# MCU.net
KiCad netlist of a schematic drawn in Altium Designer
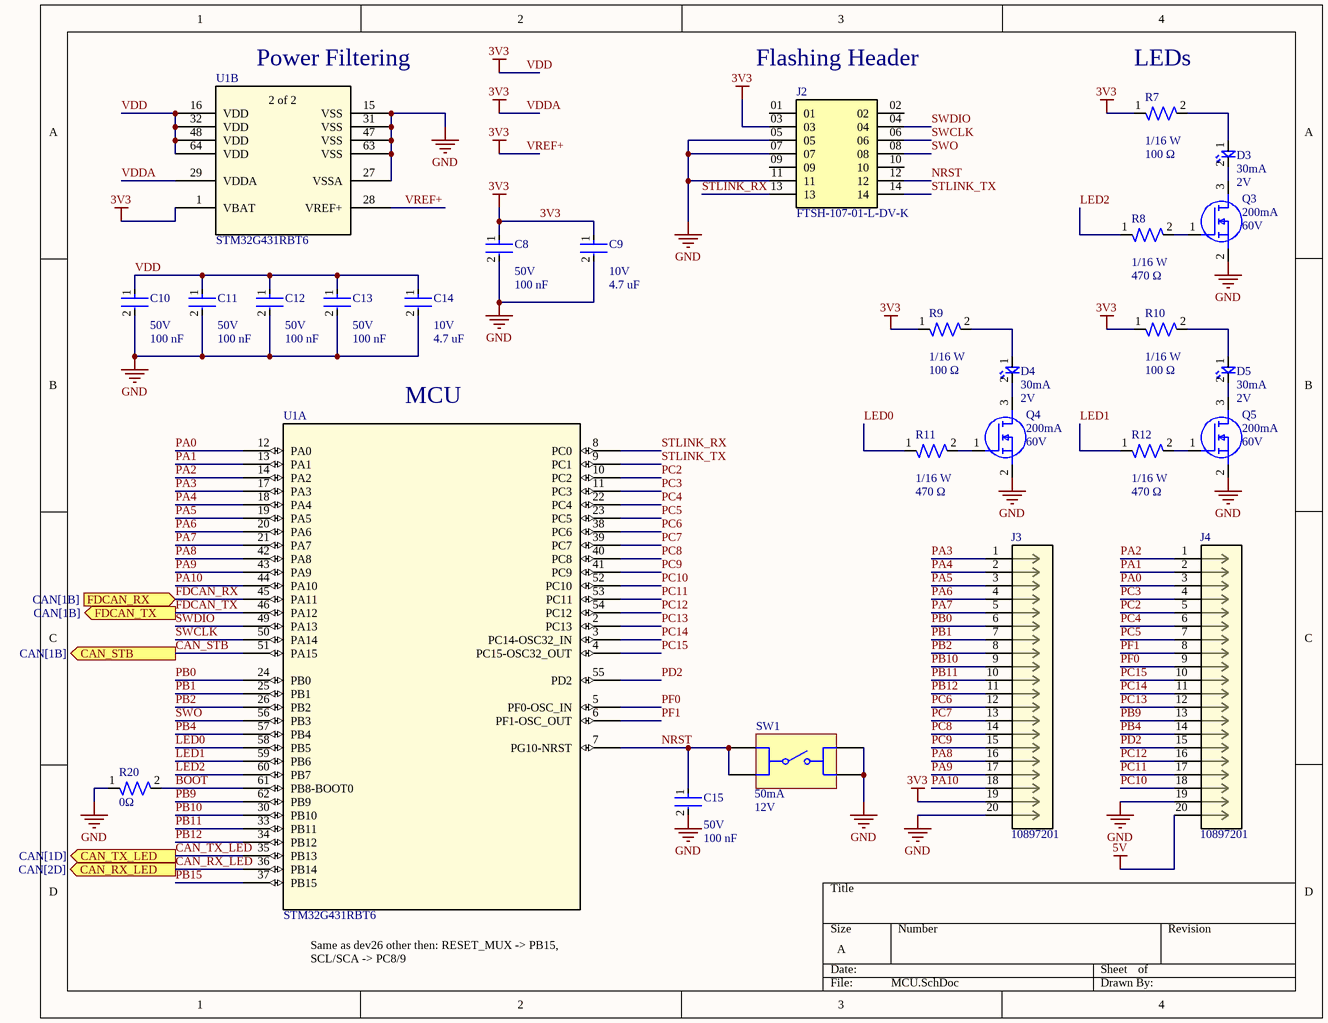
[diagram p0: MCU.SchDoc]

(export (version "E")
  (design (tool "Eeschema 10.0.6"))
  (components
    (comp (ref "C8")
      (value "CC0603ZRY5V9BB104")
      (footprint "CAP-0603")
      (fields (field (name "VOLTAGE RATING") "50V") (field (name "CAPACITANCE") "100 nF"))
      (libsource (lib "EHW_27") (part "CAP 0603"))
    )
    (comp (ref "C9")
      (value "GRM155R61A475MEAAD")
      (footprint "CAP-0402")
      (fields (field (name "VOLTAGE RATING") "10V") (field (name "CAPACITANCE") "4.7 uF"))
      (libsource (lib "EHW_27") (part "CAP 0402"))
    )
    (comp (ref "C10")
      (value "CC0603ZRY5V9BB104")
      (footprint "CAP-0603")
      (fields (field (name "VOLTAGE RATING") "50V") (field (name "CAPACITANCE") "100 nF"))
      (libsource (lib "EHW_27") (part "CAP 0603"))
    )
    (comp (ref "C11")
      (value "CC0603ZRY5V9BB104")
      (footprint "CAP-0603")
      (fields (field (name "VOLTAGE RATING") "50V") (field (name "CAPACITANCE") "100 nF"))
      (libsource (lib "EHW_27") (part "CAP 0603"))
    )
    (comp (ref "C12")
      (value "CC0603ZRY5V9BB104")
      (footprint "CAP-0603")
      (fields (field (name "VOLTAGE RATING") "50V") (field (name "CAPACITANCE") "100 nF"))
      (libsource (lib "EHW_27") (part "CAP 0603"))
    )
    (comp (ref "C13")
      (value "CC0603ZRY5V9BB104")
      (footprint "CAP-0603")
      (fields (field (name "VOLTAGE RATING") "50V") (field (name "CAPACITANCE") "100 nF"))
      (libsource (lib "EHW_27") (part "CAP 0603"))
    )
    (comp (ref "C14")
      (value "GRM155R61A475MEAAD")
      (footprint "CAP-0402")
      (fields (field (name "VOLTAGE RATING") "10V") (field (name "CAPACITANCE") "4.7 uF"))
      (libsource (lib "EHW_27") (part "CAP 0402"))
    )
    (comp (ref "C15")
      (value "CC0603ZRY5V9BB104")
      (footprint "CAP-0603")
      (fields (field (name "VOLTAGE RATING") "50V") (field (name "CAPACITANCE") "100 nF"))
      (libsource (lib "EHW_27") (part "CAP 0603"))
    )
    (comp (ref "D3")
      (value "BL-HKC36G-AV-TRB")
      (footprint "LED-0603")
      (description "LED YELLOW CLEAR 0603 SMD")
      (fields (field (name "FORWARD CURRENT") "30mA") (field (name "FORWARD VOLTAGE") "2V"))
      (libsource (lib "EHW_27") (part "LED-0001"))
    )
    (comp (ref "D4")
      (value "BL-HKC36G-AV-TRB")
      (footprint "LED-0603")
      (description "LED YELLOW CLEAR 0603 SMD")
      (fields (field (name "FORWARD CURRENT") "30mA") (field (name "FORWARD VOLTAGE") "2V"))
      (libsource (lib "EHW_27") (part "LED-0001"))
    )
    (comp (ref "D5")
      (value "BL-HKC36G-AV-TRB")
      (footprint "LED-0603")
      (description "LED YELLOW CLEAR 0603 SMD")
      (fields (field (name "FORWARD CURRENT") "30mA") (field (name "FORWARD VOLTAGE") "2V"))
      (libsource (lib "EHW_27") (part "LED-0001"))
    )
    (comp (ref "J2")
      (value "FTSH-107-01-L-DV-K")
      (footprint "SAMTEC_FTSH-107-01-L-DV-K")
      (description "Connector Header Surface Mount 14 position 0.050\" (1.27mm)")
      (fields (field (name "MF") "Samtec"))
      (libsource (lib "EHW_27") (part "CONN_Flashing-0001"))
    )
    (comp (ref "J3")
      (value "10897201")
      (footprint "CONN20_0010897201_MOL")
      (fields (field (name "COPYRIGHT") "Copyright (C) 2025 Ultra Librarian. All rights reserved."))
      (libsource (lib "EHW_27") (part "CONN-20"))
    )
    (comp (ref "J4")
      (value "10897201")
      (footprint "CONN20_0010897201_MOL")
      (fields (field (name "COPYRIGHT") "Copyright (C) 2025 Ultra Librarian. All rights reserved."))
      (libsource (lib "EHW_27") (part "CONN-20"))
    )
    (comp (ref "Q3")
      (value "T2N7002AK,LM")
      (footprint "IC-SOT23-3")
      (description "MOSFET N-CH 60V 200MA SOT23")
      (fields (field (name "CONTINUOUS CURRENT") "200mA") (field (name "VOLTAGE") "60V"))
      (libsource (lib "EHW_27") (part "NMOS-200MA-0001"))
    )
    (comp (ref "Q4")
      (value "T2N7002AK,LM")
      (footprint "IC-SOT23-3")
      (description "MOSFET N-CH 60V 200MA SOT23")
      (fields (field (name "CONTINUOUS CURRENT") "200mA") (field (name "VOLTAGE") "60V"))
      (libsource (lib "EHW_27") (part "NMOS-200MA-0001"))
    )
    (comp (ref "Q5")
      (value "T2N7002AK,LM")
      (footprint "IC-SOT23-3")
      (description "MOSFET N-CH 60V 200MA SOT23")
      (fields (field (name "CONTINUOUS CURRENT") "200mA") (field (name "VOLTAGE") "60V"))
      (libsource (lib "EHW_27") (part "NMOS-200MA-0001"))
    )
    (comp (ref "R7")
      (value "RC0402FR-07100RL")
      (footprint "RES-0402")
      (fields (field (name "WATTAGE") "1/16 W") (field (name "RESISTANCE") "100 Ω"))
      (libsource (lib "EHW_27") (part "RES 0402"))
    )
    (comp (ref "R8")
      (value "RC0402FR-07470RL")
      (footprint "RES-0402")
      (fields (field (name "WATTAGE") "1/16 W") (field (name "RESISTANCE") "470 Ω"))
      (libsource (lib "EHW_27") (part "RES 0402"))
    )
    (comp (ref "R9")
      (value "RC0402FR-07100RL")
      (footprint "RES-0402")
      (fields (field (name "WATTAGE") "1/16 W") (field (name "RESISTANCE") "100 Ω"))
      (libsource (lib "EHW_27") (part "RES 0402"))
    )
    (comp (ref "R10")
      (value "RC0402FR-07100RL")
      (footprint "RES-0402")
      (fields (field (name "WATTAGE") "1/16 W") (field (name "RESISTANCE") "100 Ω"))
      (libsource (lib "EHW_27") (part "RES 0402"))
    )
    (comp (ref "R11")
      (value "RC0402FR-07470RL")
      (footprint "RES-0402")
      (fields (field (name "WATTAGE") "1/16 W") (field (name "RESISTANCE") "470 Ω"))
      (libsource (lib "EHW_27") (part "RES 0402"))
    )
    (comp (ref "R12")
      (value "RC0402FR-07470RL")
      (footprint "RES-0402")
      (fields (field (name "WATTAGE") "1/16 W") (field (name "RESISTANCE") "470 Ω"))
      (libsource (lib "EHW_27") (part "RES 0402"))
    )
    (comp (ref "R20")
      (value "CRF2010-J/-000ELF")
      (footprint "RES-2010")
      (description "0 Ohms Jumper Chip Resistor 2010 (5025 Metric) Automotive AEC-Q200 Metal Element")
      (fields (field (name "TOLERANCE") "1%") (field (name "RESISTANCE") "0Ω"))
      (libsource (lib "EHW_27") (part "RES-0-0001"))
    )
    (comp (ref "SW1")
      (value "430182095816")
      (footprint "430182095816")
      (description "WS-TASV SMT Tact Switch, 6mm x 6mm, 160gf, SPST-NO, 12V, 50mA")
      (fields
        (field (name "MANUFACTURER") "Wurth Elektronik")
        (field (name "RATED CURRENT") "50mA")
        (field (name "RATED VOLTAGE (DC)") "12V")
      )
      (libsource (lib "EHW_27") (part "BUTTON-VERT-12V-0.5A"))
    )
    (comp (ref "U1")
      (value "STM32G431RBT6")
      (footprint "LQFP64-10x10mm")
      (fields (field (name "COPYRIGHT") "Copyright (C) 2025 Ultra Librarian. All rights reserved."))
      (libsource (lib "EHW_27") (part "IC-STM32G431RBT6"))
    )
  )
  (nets
    (net (code "1") (name "/BOOT") (class "Default")
      (node (ref "R20") (pin "2") (pinfunction "2_2") (pintype "passive"))
      (node (ref "U1") (pin "61") (pinfunction "PB8-BOOT0_61") (pintype "bidirectional"))
    )
    (net (code "2") (name "/CAN_RX_LED") (class "Default")
      (node (ref "U1") (pin "36") (pinfunction "PB14_36") (pintype "bidirectional"))
    )
    (net (code "3") (name "/CAN_STB") (class "Default")
      (node (ref "U1") (pin "51") (pinfunction "PA15_51") (pintype "bidirectional"))
    )
    (net (code "4") (name "/CAN_TX_LED") (class "Default")
      (node (ref "U1") (pin "35") (pinfunction "PB13_35") (pintype "bidirectional"))
    )
    (net (code "5") (name "/FDCAN_RX") (class "Default")
      (node (ref "U1") (pin "45") (pinfunction "PA11_45") (pintype "bidirectional"))
    )
    (net (code "6") (name "/FDCAN_TX") (class "Default")
      (node (ref "U1") (pin "46") (pinfunction "PA12_46") (pintype "bidirectional"))
    )
    (net (code "7") (name "/LED0") (class "Default")
      (node (ref "R11") (pin "1") (pinfunction "1_1") (pintype "passive"))
      (node (ref "U1") (pin "58") (pinfunction "PB5_58") (pintype "bidirectional"))
    )
    (net (code "8") (name "/LED1") (class "Default")
      (node (ref "R12") (pin "1") (pinfunction "1_1") (pintype "passive"))
      (node (ref "U1") (pin "59") (pinfunction "PB6_59") (pintype "bidirectional"))
    )
    (net (code "9") (name "/LED2") (class "Default")
      (node (ref "R8") (pin "1") (pinfunction "1_1") (pintype "passive"))
      (node (ref "U1") (pin "60") (pinfunction "PB7_60") (pintype "bidirectional"))
    )
    (net (code "10") (name "/NRST") (class "Default")
      (node (ref "C15") (pin "1") (pinfunction "1_1") (pintype "passive"))
      (node (ref "J2") (pin "12") (pinfunction "12_12") (pintype "passive"))
      (node (ref "SW1") (pin "A1") (pinfunction "A1_A1") (pintype "passive"))
      (node (ref "SW1") (pin "A2") (pinfunction "A2_A2") (pintype "passive"))
      (node (ref "U1") (pin "7") (pinfunction "PG10-NRST_7") (pintype "bidirectional"))
    )
    (net (code "11") (name "/PA0") (class "Default")
      (node (ref "J4") (pin "3") (pinfunction "3_3") (pintype "passive"))
      (node (ref "U1") (pin "12") (pinfunction "PA0_12") (pintype "bidirectional"))
    )
    (net (code "12") (name "/PA1") (class "Default")
      (node (ref "J4") (pin "2") (pinfunction "2_2") (pintype "passive"))
      (node (ref "U1") (pin "13") (pinfunction "PA1_13") (pintype "bidirectional"))
    )
    (net (code "13") (name "/PA2") (class "Default")
      (node (ref "J4") (pin "1") (pinfunction "1_1") (pintype "passive"))
      (node (ref "U1") (pin "14") (pinfunction "PA2_14") (pintype "bidirectional"))
    )
    (net (code "14") (name "/PA3") (class "Default")
      (node (ref "J3") (pin "1") (pinfunction "1_1") (pintype "passive"))
      (node (ref "U1") (pin "17") (pinfunction "PA3_17") (pintype "bidirectional"))
    )
    (net (code "15") (name "/PA4") (class "Default")
      (node (ref "J3") (pin "2") (pinfunction "2_2") (pintype "passive"))
      (node (ref "U1") (pin "18") (pinfunction "PA4_18") (pintype "bidirectional"))
    )
    (net (code "16") (name "/PA5") (class "Default")
      (node (ref "J3") (pin "3") (pinfunction "3_3") (pintype "passive"))
      (node (ref "U1") (pin "19") (pinfunction "PA5_19") (pintype "bidirectional"))
    )
    (net (code "17") (name "/PA6") (class "Default")
      (node (ref "J3") (pin "4") (pinfunction "4_4") (pintype "passive"))
      (node (ref "U1") (pin "20") (pinfunction "PA6_20") (pintype "bidirectional"))
    )
    (net (code "18") (name "/PA7") (class "Default")
      (node (ref "J3") (pin "5") (pinfunction "5_5") (pintype "passive"))
      (node (ref "U1") (pin "21") (pinfunction "PA7_21") (pintype "bidirectional"))
    )
    (net (code "19") (name "/PA8") (class "Default")
      (node (ref "J3") (pin "16") (pinfunction "16_16") (pintype "passive"))
      (node (ref "U1") (pin "42") (pinfunction "PA8_42") (pintype "bidirectional"))
    )
    (net (code "20") (name "/PA9") (class "Default")
      (node (ref "J3") (pin "17") (pinfunction "17_17") (pintype "passive"))
      (node (ref "U1") (pin "43") (pinfunction "PA9_43") (pintype "bidirectional"))
    )
    (net (code "21") (name "/PA10") (class "Default")
      (node (ref "J3") (pin "18") (pinfunction "18_18") (pintype "passive"))
      (node (ref "U1") (pin "44") (pinfunction "PA10_44") (pintype "bidirectional"))
    )
    (net (code "22") (name "/PB0") (class "Default")
      (node (ref "J3") (pin "6") (pinfunction "6_6") (pintype "passive"))
      (node (ref "U1") (pin "24") (pinfunction "PB0_24") (pintype "bidirectional"))
    )
    (net (code "23") (name "/PB1") (class "Default")
      (node (ref "J3") (pin "7") (pinfunction "7_7") (pintype "passive"))
      (node (ref "U1") (pin "25") (pinfunction "PB1_25") (pintype "bidirectional"))
    )
    (net (code "24") (name "/PB2") (class "Default")
      (node (ref "J3") (pin "8") (pinfunction "8_8") (pintype "passive"))
      (node (ref "U1") (pin "26") (pinfunction "PB2_26") (pintype "bidirectional"))
    )
    (net (code "25") (name "/PB4") (class "Default")
      (node (ref "J4") (pin "14") (pinfunction "14_14") (pintype "passive"))
      (node (ref "U1") (pin "57") (pinfunction "PB4_57") (pintype "bidirectional"))
    )
    (net (code "26") (name "/PB9") (class "Default")
      (node (ref "J4") (pin "13") (pinfunction "13_13") (pintype "passive"))
      (node (ref "U1") (pin "62") (pinfunction "PB9_62") (pintype "bidirectional"))
    )
    (net (code "27") (name "/PB10") (class "Default")
      (node (ref "J3") (pin "9") (pinfunction "9_9") (pintype "passive"))
      (node (ref "U1") (pin "30") (pinfunction "PB10_30") (pintype "bidirectional"))
    )
    (net (code "28") (name "/PB11") (class "Default")
      (node (ref "J3") (pin "10") (pinfunction "10_10") (pintype "passive"))
      (node (ref "U1") (pin "33") (pinfunction "PB11_33") (pintype "bidirectional"))
    )
    (net (code "29") (name "/PB12") (class "Default")
      (node (ref "J3") (pin "11") (pinfunction "11_11") (pintype "passive"))
      (node (ref "U1") (pin "34") (pinfunction "PB12_34") (pintype "bidirectional"))
    )
    (net (code "30") (name "/PB15") (class "Default")
      (node (ref "U1") (pin "37") (pinfunction "PB15_37") (pintype "bidirectional"))
    )
    (net (code "31") (name "/PC2") (class "Default")
      (node (ref "J4") (pin "5") (pinfunction "5_5") (pintype "passive"))
      (node (ref "U1") (pin "10") (pinfunction "PC2_10") (pintype "bidirectional"))
    )
    (net (code "32") (name "/PC3") (class "Default")
      (node (ref "J4") (pin "4") (pinfunction "4_4") (pintype "passive"))
      (node (ref "U1") (pin "11") (pinfunction "PC3_11") (pintype "bidirectional"))
    )
    (net (code "33") (name "/PC4") (class "Default")
      (node (ref "J4") (pin "6") (pinfunction "6_6") (pintype "passive"))
      (node (ref "U1") (pin "22") (pinfunction "PC4_22") (pintype "bidirectional"))
    )
    (net (code "34") (name "/PC5") (class "Default")
      (node (ref "J4") (pin "7") (pinfunction "7_7") (pintype "passive"))
      (node (ref "U1") (pin "23") (pinfunction "PC5_23") (pintype "bidirectional"))
    )
    (net (code "35") (name "/PC6") (class "Default")
      (node (ref "J3") (pin "12") (pinfunction "12_12") (pintype "passive"))
      (node (ref "U1") (pin "38") (pinfunction "PC6_38") (pintype "bidirectional"))
    )
    (net (code "36") (name "/PC7") (class "Default")
      (node (ref "J3") (pin "13") (pinfunction "13_13") (pintype "passive"))
      (node (ref "U1") (pin "39") (pinfunction "PC7_39") (pintype "bidirectional"))
    )
    (net (code "37") (name "/PC8") (class "Default")
      (node (ref "J3") (pin "14") (pinfunction "14_14") (pintype "passive"))
      (node (ref "U1") (pin "40") (pinfunction "PC8_40") (pintype "bidirectional"))
    )
    (net (code "38") (name "/PC9") (class "Default")
      (node (ref "J3") (pin "15") (pinfunction "15_15") (pintype "passive"))
      (node (ref "U1") (pin "41") (pinfunction "PC9_41") (pintype "bidirectional"))
    )
    (net (code "39") (name "/PC10") (class "Default")
      (node (ref "J4") (pin "18") (pinfunction "18_18") (pintype "passive"))
      (node (ref "U1") (pin "52") (pinfunction "PC10_52") (pintype "bidirectional"))
    )
    (net (code "40") (name "/PC11") (class "Default")
      (node (ref "J4") (pin "17") (pinfunction "17_17") (pintype "passive"))
      (node (ref "U1") (pin "53") (pinfunction "PC11_53") (pintype "bidirectional"))
    )
    (net (code "41") (name "/PC12") (class "Default")
      (node (ref "J4") (pin "16") (pinfunction "16_16") (pintype "passive"))
      (node (ref "U1") (pin "54") (pinfunction "PC12_54") (pintype "bidirectional"))
    )
    (net (code "42") (name "/PC13") (class "Default")
      (node (ref "J4") (pin "12") (pinfunction "12_12") (pintype "passive"))
      (node (ref "U1") (pin "2") (pinfunction "PC13_2") (pintype "bidirectional"))
    )
    (net (code "43") (name "/PC14") (class "Default")
      (node (ref "J4") (pin "11") (pinfunction "11_11") (pintype "passive"))
      (node (ref "U1") (pin "3") (pinfunction "PC14-OSC32_IN_3") (pintype "bidirectional"))
    )
    (net (code "44") (name "/PC15") (class "Default")
      (node (ref "J4") (pin "10") (pinfunction "10_10") (pintype "passive"))
      (node (ref "U1") (pin "4") (pinfunction "PC15-OSC32_OUT_4") (pintype "bidirectional"))
    )
    (net (code "45") (name "/PD2") (class "Default")
      (node (ref "J4") (pin "15") (pinfunction "15_15") (pintype "passive"))
      (node (ref "U1") (pin "55") (pinfunction "PD2_55") (pintype "bidirectional"))
    )
    (net (code "46") (name "/PF0") (class "Default")
      (node (ref "J4") (pin "9") (pinfunction "9_9") (pintype "passive"))
      (node (ref "U1") (pin "5") (pinfunction "PF0-OSC_IN_5") (pintype "bidirectional"))
    )
    (net (code "47") (name "/PF1") (class "Default")
      (node (ref "J4") (pin "8") (pinfunction "8_8") (pintype "passive"))
      (node (ref "U1") (pin "6") (pinfunction "PF1-OSC_OUT_6") (pintype "bidirectional"))
    )
    (net (code "48") (name "/STLINK_RX") (class "Default")
      (node (ref "J2") (pin "13") (pinfunction "13_13") (pintype "passive"))
      (node (ref "U1") (pin "8") (pinfunction "PC0_8") (pintype "bidirectional"))
    )
    (net (code "49") (name "/STLINK_TX") (class "Default")
      (node (ref "J2") (pin "14") (pinfunction "14_14") (pintype "passive"))
      (node (ref "U1") (pin "9") (pinfunction "PC1_9") (pintype "bidirectional"))
    )
    (net (code "50") (name "/SWCLK") (class "Default")
      (node (ref "J2") (pin "06") (pinfunction "06_06") (pintype "passive"))
      (node (ref "U1") (pin "50") (pinfunction "PA14_50") (pintype "bidirectional"))
    )
    (net (code "51") (name "/SWDIO") (class "Default")
      (node (ref "J2") (pin "04") (pinfunction "04_04") (pintype "passive"))
      (node (ref "U1") (pin "49") (pinfunction "PA13_49") (pintype "bidirectional"))
    )
    (net (code "52") (name "/SWO") (class "Default")
      (node (ref "J2") (pin "08") (pinfunction "08_08") (pintype "passive"))
      (node (ref "U1") (pin "56") (pinfunction "PB3_56") (pintype "bidirectional"))
    )
    (net (code "53") (name "3V3") (class "Default")
      (node (ref "C10") (pin "1") (pinfunction "1_1") (pintype "passive"))
      (node (ref "C11") (pin "1") (pinfunction "1_1") (pintype "passive"))
      (node (ref "C12") (pin "1") (pinfunction "1_1") (pintype "passive"))
      (node (ref "C13") (pin "1") (pinfunction "1_1") (pintype "passive"))
      (node (ref "C14") (pin "1") (pinfunction "1_1") (pintype "passive"))
      (node (ref "C8") (pin "1") (pinfunction "1_1") (pintype "passive"))
      (node (ref "C9") (pin "1") (pinfunction "1_1") (pintype "passive"))
      (node (ref "J2") (pin "03") (pinfunction "03_03") (pintype "passive"))
      (node (ref "J3") (pin "19") (pinfunction "19_19") (pintype "passive"))
      (node (ref "R10") (pin "1") (pinfunction "1_1") (pintype "passive"))
      (node (ref "R7") (pin "1") (pinfunction "1_1") (pintype "passive"))
      (node (ref "R9") (pin "1") (pinfunction "1_1") (pintype "passive"))
      (node (ref "U1") (pin "1") (pinfunction "VBAT_1") (pintype "power_in"))
      (node (ref "U1") (pin "16") (pinfunction "VDD_16") (pintype "power_in"))
      (node (ref "U1") (pin "28") (pinfunction "VREF+_28") (pintype "power_in"))
      (node (ref "U1") (pin "29") (pinfunction "VDDA_29") (pintype "power_in"))
      (node (ref "U1") (pin "32") (pinfunction "VDD_32") (pintype "power_in"))
      (node (ref "U1") (pin "48") (pinfunction "VDD_48") (pintype "power_in"))
      (node (ref "U1") (pin "64") (pinfunction "VDD_64") (pintype "power_in"))
    )
    (net (code "54") (name "5V") (class "Default")
      (node (ref "J4") (pin "20") (pinfunction "20_20") (pintype "passive"))
    )
    (net (code "55") (name "GND") (class "Default")
      (node (ref "C10") (pin "2") (pinfunction "2_2") (pintype "passive"))
      (node (ref "C11") (pin "2") (pinfunction "2_2") (pintype "passive"))
      (node (ref "C12") (pin "2") (pinfunction "2_2") (pintype "passive"))
      (node (ref "C13") (pin "2") (pinfunction "2_2") (pintype "passive"))
      (node (ref "C14") (pin "2") (pinfunction "2_2") (pintype "passive"))
      (node (ref "C15") (pin "2") (pinfunction "2_2") (pintype "passive"))
      (node (ref "C8") (pin "2") (pinfunction "2_2") (pintype "passive"))
      (node (ref "C9") (pin "2") (pinfunction "2_2") (pintype "passive"))
      (node (ref "J2") (pin "05") (pinfunction "05_05") (pintype "passive"))
      (node (ref "J2") (pin "07") (pinfunction "07_07") (pintype "passive"))
      (node (ref "J2") (pin "11") (pinfunction "11_11") (pintype "passive"))
      (node (ref "J3") (pin "20") (pinfunction "20_20") (pintype "passive"))
      (node (ref "J4") (pin "19") (pinfunction "19_19") (pintype "passive"))
      (node (ref "Q3") (pin "2") (pinfunction "S_2") (pintype "passive"))
      (node (ref "Q4") (pin "2") (pinfunction "S_2") (pintype "passive"))
      (node (ref "Q5") (pin "2") (pinfunction "S_2") (pintype "passive"))
      (node (ref "R20") (pin "1") (pinfunction "1_1") (pintype "passive"))
      (node (ref "SW1") (pin "B1") (pinfunction "B1_B1") (pintype "passive"))
      (node (ref "SW1") (pin "B2") (pinfunction "B2_B2") (pintype "passive"))
      (node (ref "U1") (pin "15") (pinfunction "VSS_15") (pintype "power_in"))
      (node (ref "U1") (pin "27") (pinfunction "VSSA_27") (pintype "power_in"))
      (node (ref "U1") (pin "31") (pinfunction "VSS_31") (pintype "power_in"))
      (node (ref "U1") (pin "47") (pinfunction "VSS_47") (pintype "power_in"))
      (node (ref "U1") (pin "63") (pinfunction "VSS_63") (pintype "power_in"))
    )
    (net (code "56") (name "Net-(D3-Pad1)") (class "Default")
      (node (ref "D3") (pin "1") (pinfunction "1_1") (pintype "passive"))
      (node (ref "R7") (pin "2") (pinfunction "2_2") (pintype "passive"))
    )
    (net (code "57") (name "Net-(D4-Pad1)") (class "Default")
      (node (ref "D4") (pin "1") (pinfunction "1_1") (pintype "passive"))
      (node (ref "R9") (pin "2") (pinfunction "2_2") (pintype "passive"))
    )
    (net (code "58") (name "Net-(D5-Pad1)") (class "Default")
      (node (ref "D5") (pin "1") (pinfunction "1_1") (pintype "passive"))
      (node (ref "R10") (pin "2") (pinfunction "2_2") (pintype "passive"))
    )
    (net (code "59") (name "Net-(Q3-D)") (class "Default")
      (node (ref "D3") (pin "2") (pinfunction "2_2") (pintype "passive"))
      (node (ref "Q3") (pin "3") (pinfunction "D_3") (pintype "passive"))
    )
    (net (code "60") (name "Net-(Q3-G)") (class "Default")
      (node (ref "Q3") (pin "1") (pinfunction "G_1") (pintype "passive"))
      (node (ref "R8") (pin "2") (pinfunction "2_2") (pintype "passive"))
    )
    (net (code "61") (name "Net-(Q4-D)") (class "Default")
      (node (ref "D4") (pin "2") (pinfunction "2_2") (pintype "passive"))
      (node (ref "Q4") (pin "3") (pinfunction "D_3") (pintype "passive"))
    )
    (net (code "62") (name "Net-(Q4-G)") (class "Default")
      (node (ref "Q4") (pin "1") (pinfunction "G_1") (pintype "passive"))
      (node (ref "R11") (pin "2") (pinfunction "2_2") (pintype "passive"))
    )
    (net (code "63") (name "Net-(Q5-D)") (class "Default")
      (node (ref "D5") (pin "2") (pinfunction "2_2") (pintype "passive"))
      (node (ref "Q5") (pin "3") (pinfunction "D_3") (pintype "passive"))
    )
    (net (code "64") (name "Net-(Q5-G)") (class "Default")
      (node (ref "Q5") (pin "1") (pinfunction "G_1") (pintype "passive"))
      (node (ref "R12") (pin "2") (pinfunction "2_2") (pintype "passive"))
    )
    (net (code "65") (name "unconnected-(J2-Pad01)") (class "Default")
      (node (ref "J2") (pin "01") (pinfunction "01_01") (pintype "passive"))
    )
    (net (code "66") (name "unconnected-(J2-Pad02)") (class "Default")
      (node (ref "J2") (pin "02") (pinfunction "02_02") (pintype "passive"))
    )
    (net (code "67") (name "unconnected-(J2-Pad09)") (class "Default")
      (node (ref "J2") (pin "09") (pinfunction "09_09") (pintype "passive"))
    )
    (net (code "68") (name "unconnected-(J2-Pad10)") (class "Default")
      (node (ref "J2") (pin "10") (pinfunction "10_10") (pintype "passive"))
    )
  )
)
